# PowerAmplifier_Control.net
KiCad netlist of a schematic drawn in Altium Designer
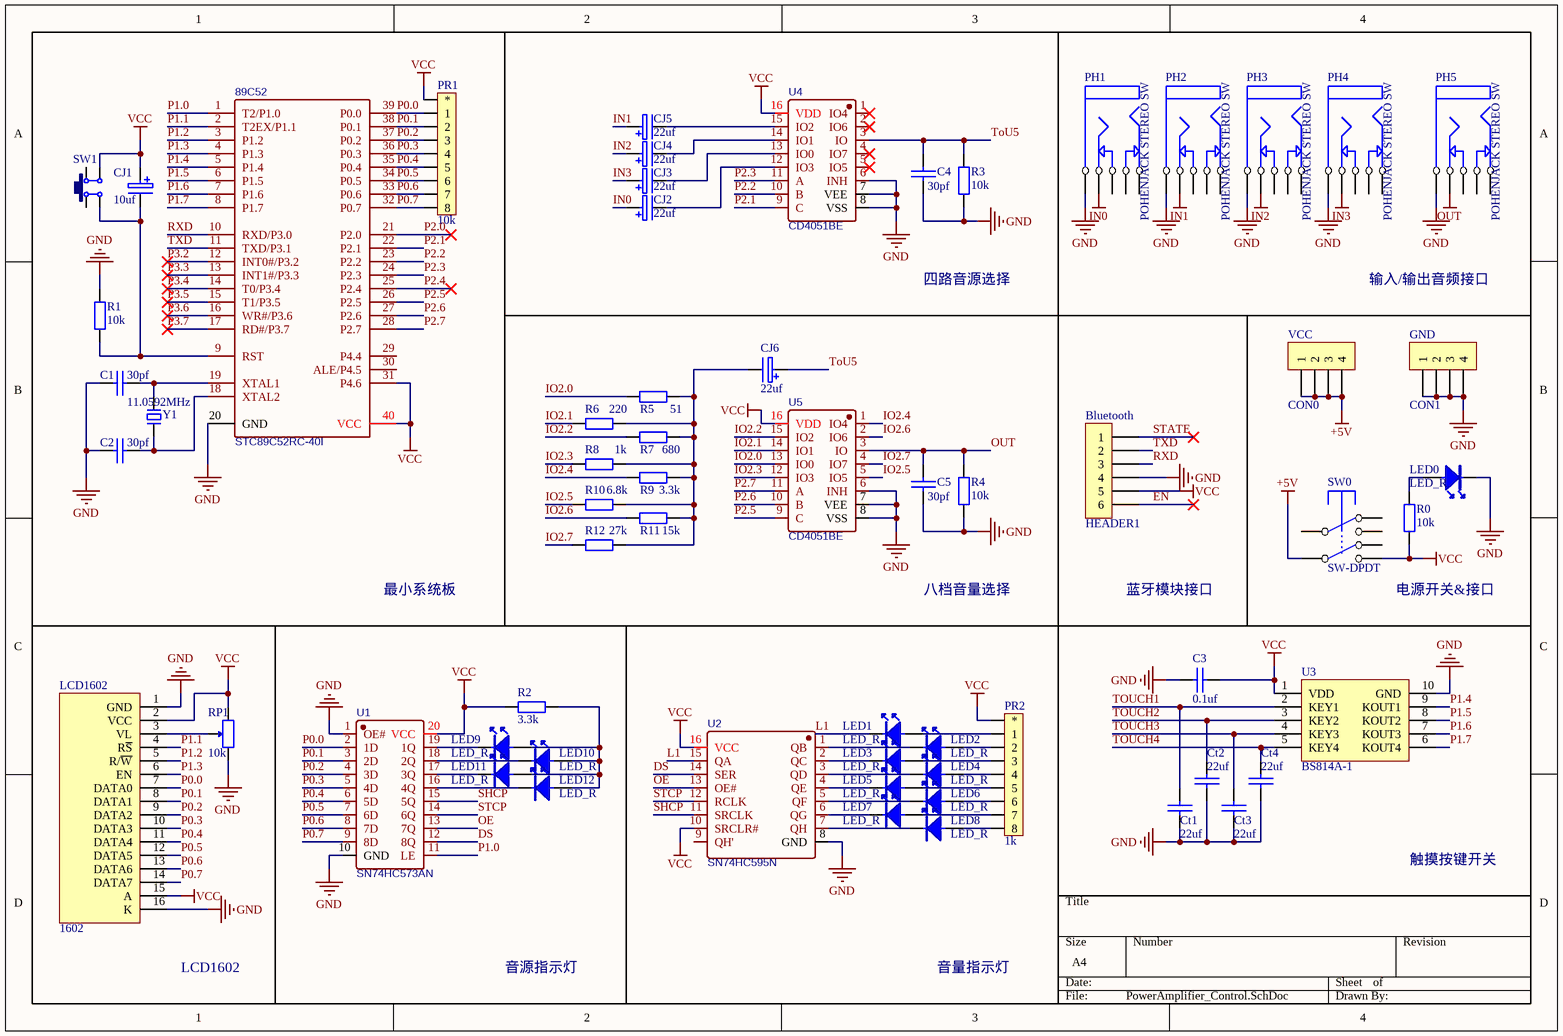
[diagram p0: PowerAmplifier_Control.SchDoc]

(export (version "E")
  (design (tool "Eeschema 10.0.6"))
  (components
    (comp (ref "89C52")
      (value "STC89C52RC-40I")
      (footprint "DIP-40_LS15.24-L52.58-W13.97-PITCH2.54")
      (fields (field (name "BOM_SUPPLIER PART") "C14022"))
      (libsource (lib "电子时钟元件库") (part "STC89C52RC-40I"))
    )
    (comp (ref "Bluetooth")
      (value "HEADER1")
      (footprint "sip-6")
      (description "Connector")
      (libsource (lib "基地库3.0mini") (part "CON6"))
    )
    (comp (ref "C1") (value "30pf") (footprint "1206") (libsource (lib "基地库3.0mini") (part "CAP1")))
    (comp (ref "C2") (value "30pf") (footprint "1206") (libsource (lib "基地库3.0mini") (part "CAP1")))
    (comp (ref "C3") (value "0.1uf") (footprint "1206") (libsource (lib "基地库3.0mini") (part "CAP1")))
    (comp (ref "C4") (value "30pf") (footprint "1206") (libsource (lib "基地库3.0mini") (part "CAP1")))
    (comp (ref "C5") (value "30pf") (footprint "1206") (libsource (lib "基地库3.0mini") (part "CAP1")))
    (comp (ref "CJ1") (value "10uf") (footprint "CAO1") (libsource (lib "基地库3.0mini") (part "CAP3")))
    (comp (ref "CJ2") (value "22uf") (footprint "CAO1") (libsource (lib "基地库3.0mini") (part "CAP3")))
    (comp (ref "CJ3") (value "22uf") (footprint "CAO1") (libsource (lib "基地库3.0mini") (part "CAP3")))
    (comp (ref "CJ4") (value "22uf") (footprint "CAO1") (libsource (lib "基地库3.0mini") (part "CAP3")))
    (comp (ref "CJ5") (value "22uf") (footprint "CAO1") (libsource (lib "基地库3.0mini") (part "CAP3")))
    (comp (ref "CJ6") (value "22uf") (footprint "CAO1") (libsource (lib "基地库3.0mini") (part "CAP3")))
    (comp (ref "Ct1") (value "22uf") (footprint "1206") (libsource (lib "基地库3.0mini") (part "CAP1")))
    (comp (ref "Ct2") (value "22uf") (footprint "1206") (libsource (lib "基地库3.0mini") (part "CAP1")))
    (comp (ref "Ct3") (value "22uf") (footprint "1206") (libsource (lib "基地库3.0mini") (part "CAP1")))
    (comp (ref "Ct4") (value "22uf") (footprint "1206") (libsource (lib "基地库3.0mini") (part "CAP1")))
    (comp (ref "GND")
      (value "CON1")
      (footprint "sip-4")
      (description "Connector")
      (libsource (lib "基地库3.0mini") (part "CON4"))
    )
    (comp (ref "LCD1602") (value "1602") (footprint "1602") (libsource (lib "基地库3.0mini") (part "1602")))
    (comp (ref "LED0") (value "LED_R") (footprint "LED_1206") (libsource (lib "基地库3.0mini") (part "LED")))
    (comp (ref "LED1") (value "LED_R") (footprint "LED_1206") (libsource (lib "基地库3.0mini") (part "LED")))
    (comp (ref "LED2") (value "LED_R") (footprint "LED_1206") (libsource (lib "基地库3.0mini") (part "LED")))
    (comp (ref "LED3") (value "LED_R") (footprint "LED_1206") (libsource (lib "基地库3.0mini") (part "LED")))
    (comp (ref "LED4") (value "LED_R") (footprint "LED_1206") (libsource (lib "基地库3.0mini") (part "LED")))
    (comp (ref "LED5") (value "LED_R") (footprint "LED_1206") (libsource (lib "基地库3.0mini") (part "LED")))
    (comp (ref "LED6") (value "LED_R") (footprint "LED_1206") (libsource (lib "基地库3.0mini") (part "LED")))
    (comp (ref "LED7") (value "LED_R") (footprint "LED_1206") (libsource (lib "基地库3.0mini") (part "LED")))
    (comp (ref "LED8") (value "LED_R") (footprint "LED_1206") (libsource (lib "基地库3.0mini") (part "LED")))
    (comp (ref "LED9") (value "LED_R") (footprint "LED_1206") (libsource (lib "基地库3.0mini") (part "LED")))
    (comp (ref "LED10") (value "LED_R") (footprint "LED_1206") (libsource (lib "基地库3.0mini") (part "LED")))
    (comp (ref "LED11") (value "LED_R") (footprint "LED_1206") (libsource (lib "基地库3.0mini") (part "LED")))
    (comp (ref "LED12") (value "LED_R") (footprint "LED_1206") (libsource (lib "基地库3.0mini") (part "LED")))
    (comp (ref "PH1")
      (value "POHENJACK STEREO SW")
      (footprint "POHENJACK STEREO SW")
      (libsource (lib "电子电路集成库") (part "POHENJACK STEREO SW"))
    )
    (comp (ref "PH2")
      (value "POHENJACK STEREO SW")
      (footprint "POHENJACK STEREO SW")
      (libsource (lib "电子电路集成库") (part "POHENJACK STEREO SW"))
    )
    (comp (ref "PH3")
      (value "POHENJACK STEREO SW")
      (footprint "POHENJACK STEREO SW")
      (libsource (lib "电子电路集成库") (part "POHENJACK STEREO SW"))
    )
    (comp (ref "PH4")
      (value "POHENJACK STEREO SW")
      (footprint "POHENJACK STEREO SW")
      (libsource (lib "电子电路集成库") (part "POHENJACK STEREO SW"))
    )
    (comp (ref "PH5")
      (value "POHENJACK STEREO SW")
      (footprint "POHENJACK STEREO SW")
      (libsource (lib "电子电路集成库") (part "POHENJACK STEREO SW"))
    )
    (comp (ref "PR1") (value "10k") (footprint "RP1") (libsource (lib "基地库3.0mini") (part "PRES1")))
    (comp (ref "PR2") (value "1k") (footprint "RP1") (libsource (lib "基地库3.0mini") (part "PRES1")))
    (comp (ref "R0")
      (value "10k")
      (footprint "AXIAL0.4")
      (description "贴片电阻")
      (fields (field (name "版权归属") "源创客"))
      (libsource (lib "9-电阻-电容-电感") (part "R"))
    )
    (comp (ref "R1")
      (value "10k")
      (footprint "AXIAL0.4")
      (description "贴片电阻")
      (fields (field (name "版权归属") "源创客"))
      (libsource (lib "9-电阻-电容-电感") (part "R"))
    )
    (comp (ref "R2")
      (value "3.3k")
      (footprint "AXIAL0.4")
      (description "贴片电阻")
      (fields (field (name "版权归属") "源创客"))
      (libsource (lib "9-电阻-电容-电感") (part "R"))
    )
    (comp (ref "R3")
      (value "10k")
      (footprint "AXIAL0.4")
      (description "贴片电阻")
      (fields (field (name "版权归属") "源创客"))
      (libsource (lib "9-电阻-电容-电感") (part "R"))
    )
    (comp (ref "R4")
      (value "10k")
      (footprint "AXIAL0.4")
      (description "贴片电阻")
      (fields (field (name "版权归属") "源创客"))
      (libsource (lib "9-电阻-电容-电感") (part "R"))
    )
    (comp (ref "R5")
      (value "51")
      (footprint "AXIAL0.4")
      (description "贴片电阻")
      (fields (field (name "版权归属") "源创客"))
      (libsource (lib "9-电阻-电容-电感") (part "R"))
    )
    (comp (ref "R6")
      (value "220")
      (footprint "AXIAL0.4")
      (description "贴片电阻")
      (fields (field (name "版权归属") "源创客"))
      (libsource (lib "9-电阻-电容-电感") (part "R"))
    )
    (comp (ref "R7")
      (value "680")
      (footprint "AXIAL0.4")
      (description "贴片电阻")
      (fields (field (name "版权归属") "源创客"))
      (libsource (lib "9-电阻-电容-电感") (part "R"))
    )
    (comp (ref "R8")
      (value "1k")
      (footprint "AXIAL0.4")
      (description "贴片电阻")
      (fields (field (name "版权归属") "源创客"))
      (libsource (lib "9-电阻-电容-电感") (part "R"))
    )
    (comp (ref "R9")
      (value "3.3k")
      (footprint "AXIAL0.4")
      (description "贴片电阻")
      (fields (field (name "版权归属") "源创客"))
      (libsource (lib "9-电阻-电容-电感") (part "R"))
    )
    (comp (ref "R10")
      (value "6.8k")
      (footprint "AXIAL0.4")
      (description "贴片电阻")
      (fields (field (name "版权归属") "源创客"))
      (libsource (lib "9-电阻-电容-电感") (part "R"))
    )
    (comp (ref "R11")
      (value "15k")
      (footprint "AXIAL0.4")
      (description "贴片电阻")
      (fields (field (name "版权归属") "源创客"))
      (libsource (lib "9-电阻-电容-电感") (part "R"))
    )
    (comp (ref "R12")
      (value "27k")
      (footprint "AXIAL0.4")
      (description "贴片电阻")
      (fields (field (name "版权归属") "源创客"))
      (libsource (lib "9-电阻-电容-电感") (part "R"))
    )
    (comp (ref "RP1")
      (value "10k")
      (footprint "3296W")
      (description "插件单联电位器")
      (fields (field (name "版权归属") "源创客"))
      (libsource (lib "9-电阻-电容-电感") (part "RP-ID"))
    )
    (comp (ref "SW0") (value "SW-DPDT") (footprint "SWH7*7") (libsource (lib "基地库3.0mini") (part "SW-DPDT")))
    (comp (ref "SW1")
      (value "6x6x5")
      (footprint "TSW DIP-6*6*6")
      (description "直插6x6轻触开关")
      (fields (field (name "版权归属") "源创客"))
      (libsource (lib "5-按键-开关") (part "TSW DIP-6x6"))
    )
    (comp (ref "U1")
      (value "SN74HC573AN")
      (footprint "DIP-20_L26.8-W6.4-P2.54-LS7.6-BL")
      (fields (field (name "BOM_SUPPLIER PART") "C5196"))
      (libsource (lib "74HC573AN") (part "SN74HC573AN"))
    )
    (comp (ref "U2")
      (value "SN74HC595N")
      (footprint "DIP-16_L19.8-W6.5-P2.54-LS7.6-BL")
      (fields (field (name "BOM_SUPPLIER PART") "C78711"))
      (libsource (lib "74HC595N") (part "SN74HC595N"))
    )
    (comp (ref "U3")
      (value "BS814A-1")
      (footprint "MSOP10_N")
      (description "4键电容触摸按键芯片")
      (fields (field (name "版权归属") "源创客"))
      (libsource (lib "14-IC芯片") (part "BS814A"))
    )
    (comp (ref "U4")
      (value "CD4051BE")
      (footprint "DIP-16_L20.0-W6.4-P2.54-LS7.6-BL")
      (fields (field (name "BOM_SUPPLIER PART") "C5200"))
      (libsource (lib "CD4051BE") (part "CD4051BE"))
    )
    (comp (ref "U5")
      (value "CD4051BE")
      (footprint "DIP-16_L20.0-W6.4-P2.54-LS7.6-BL")
      (fields (field (name "BOM_SUPPLIER PART") "C5200"))
      (libsource (lib "CD4051BE") (part "CD4051BE"))
    )
    (comp (ref "VCC")
      (value "CON0")
      (footprint "sip-4")
      (description "Connector")
      (libsource (lib "基地库3.0mini") (part "CON4"))
    )
    (comp (ref "Y1")
      (value "11.0592MHz")
      (footprint "OSC HC-49S")
      (description "2脚无源脚晶振")
      (fields (field (name "版权归属") "源创客"))
      (libsource (lib "6-保险丝-晶振") (part "XTAL-2P"))
    )
  )
  (nets
    (net (code "1") (name "+5V") (class "Default")
      (node (ref "SW0") (pin "5") (pinfunction "5_5") (pintype "passive"))
      (node (ref "VCC") (pin "1") (pinfunction "1_1") (pintype "passive"))
      (node (ref "VCC") (pin "2") (pinfunction "2_2") (pintype "passive"))
      (node (ref "VCC") (pin "3") (pinfunction "3_3") (pintype "passive"))
      (node (ref "VCC") (pin "4") (pinfunction "4_4") (pintype "passive"))
    )
    (net (code "2") (name "/DS") (class "Default")
      (node (ref "U1") (pin "12") (pinfunction "8Q_12") (pintype "passive"))
      (node (ref "U2") (pin "14") (pinfunction "SER_14") (pintype "passive"))
    )
    (net (code "3") (name "/EN") (class "Default")
      (node (ref "Bluetooth") (pin "6") (pinfunction "6_6") (pintype "passive+no_connect"))
    )
    (net (code "4") (name "/IO2.0") (class "Default")
      (node (ref "R5") (pin "1") (pinfunction "1_1") (pintype "passive"))
      (node (ref "U5") (pin "13") (pinfunction "IO0_13") (pintype "passive"))
    )
    (net (code "5") (name "/IO2.1") (class "Default")
      (node (ref "R6") (pin "1") (pinfunction "1_1") (pintype "passive"))
      (node (ref "U5") (pin "14") (pinfunction "IO1_14") (pintype "passive"))
    )
    (net (code "6") (name "/IO2.2") (class "Default")
      (node (ref "R7") (pin "1") (pinfunction "1_1") (pintype "passive"))
      (node (ref "U5") (pin "15") (pinfunction "IO2_15") (pintype "passive"))
    )
    (net (code "7") (name "/IO2.3") (class "Default")
      (node (ref "R8") (pin "1") (pinfunction "1_1") (pintype "passive"))
      (node (ref "U5") (pin "12") (pinfunction "IO3_12") (pintype "passive"))
    )
    (net (code "8") (name "/IO2.4") (class "Default")
      (node (ref "R9") (pin "1") (pinfunction "1_1") (pintype "passive"))
      (node (ref "U5") (pin "1") (pinfunction "IO4_1") (pintype "passive"))
    )
    (net (code "9") (name "/IO2.5") (class "Default")
      (node (ref "R10") (pin "1") (pinfunction "1_1") (pintype "passive"))
      (node (ref "U5") (pin "5") (pinfunction "IO5_5") (pintype "passive"))
    )
    (net (code "10") (name "/IO2.6") (class "Default")
      (node (ref "R11") (pin "1") (pinfunction "1_1") (pintype "passive"))
      (node (ref "U5") (pin "2") (pinfunction "IO6_2") (pintype "passive"))
    )
    (net (code "11") (name "/IO2.7") (class "Default")
      (node (ref "R12") (pin "1") (pinfunction "1_1") (pintype "passive"))
      (node (ref "U5") (pin "4") (pinfunction "IO7_4") (pintype "passive"))
    )
    (net (code "12") (name "/L1") (class "Default")
      (node (ref "LED1") (pin "2") (pinfunction "2_2") (pintype "passive"))
      (node (ref "U2") (pin "15") (pinfunction "QA_15") (pintype "passive"))
    )
    (net (code "13") (name "/OE") (class "Default")
      (node (ref "U1") (pin "13") (pinfunction "7Q_13") (pintype "passive"))
      (node (ref "U2") (pin "13") (pinfunction "OE#_13") (pintype "passive"))
    )
    (net (code "14") (name "/P0.0") (class "Default")
      (node (ref "89C52") (pin "39") (pinfunction "P0.0_39") (pintype "passive"))
      (node (ref "LCD1602") (pin "7") (pinfunction "DATA0_7") (pintype "passive"))
      (node (ref "PR1") (pin "2") (pinfunction "1_2") (pintype "passive"))
      (node (ref "U1") (pin "2") (pinfunction "1D_2") (pintype "passive"))
    )
    (net (code "15") (name "/P0.1") (class "Default")
      (node (ref "89C52") (pin "38") (pinfunction "P0.1_38") (pintype "passive"))
      (node (ref "LCD1602") (pin "8") (pinfunction "DATA1_8") (pintype "passive"))
      (node (ref "PR1") (pin "3") (pinfunction "2_3") (pintype "passive"))
      (node (ref "U1") (pin "3") (pinfunction "2D_3") (pintype "passive"))
    )
    (net (code "16") (name "/P0.2") (class "Default")
      (node (ref "89C52") (pin "37") (pinfunction "P0.2_37") (pintype "passive"))
      (node (ref "LCD1602") (pin "9") (pinfunction "DATA2_9") (pintype "passive"))
      (node (ref "PR1") (pin "4") (pinfunction "3_4") (pintype "passive"))
      (node (ref "U1") (pin "4") (pinfunction "3D_4") (pintype "passive"))
    )
    (net (code "17") (name "/P0.3") (class "Default")
      (node (ref "89C52") (pin "36") (pinfunction "P0.3_36") (pintype "passive"))
      (node (ref "LCD1602") (pin "10") (pinfunction "DATA3_10") (pintype "passive"))
      (node (ref "PR1") (pin "5") (pinfunction "4_5") (pintype "passive"))
      (node (ref "U1") (pin "5") (pinfunction "4D_5") (pintype "passive"))
    )
    (net (code "18") (name "/P0.4") (class "Default")
      (node (ref "89C52") (pin "35") (pinfunction "P0.4_35") (pintype "passive"))
      (node (ref "LCD1602") (pin "11") (pinfunction "DATA4_11") (pintype "passive"))
      (node (ref "PR1") (pin "6") (pinfunction "5_6") (pintype "passive"))
      (node (ref "U1") (pin "6") (pinfunction "5D_6") (pintype "passive"))
    )
    (net (code "19") (name "/P0.5") (class "Default")
      (node (ref "89C52") (pin "34") (pinfunction "P0.5_34") (pintype "passive"))
      (node (ref "LCD1602") (pin "12") (pinfunction "DATA5_12") (pintype "passive"))
      (node (ref "PR1") (pin "7") (pinfunction "6_7") (pintype "passive"))
      (node (ref "U1") (pin "7") (pinfunction "6D_7") (pintype "passive"))
    )
    (net (code "20") (name "/P0.6") (class "Default")
      (node (ref "89C52") (pin "33") (pinfunction "P0.6_33") (pintype "passive"))
      (node (ref "LCD1602") (pin "13") (pinfunction "DATA6_13") (pintype "passive"))
      (node (ref "PR1") (pin "8") (pinfunction "7_8") (pintype "passive"))
      (node (ref "U1") (pin "8") (pinfunction "7D_8") (pintype "passive"))
    )
    (net (code "21") (name "/P0.7") (class "Default")
      (node (ref "89C52") (pin "32") (pinfunction "P0.7_32") (pintype "passive"))
      (node (ref "LCD1602") (pin "14") (pinfunction "DATA7_14") (pintype "passive"))
      (node (ref "PR1") (pin "9") (pinfunction "8_9") (pintype "passive"))
      (node (ref "U1") (pin "9") (pinfunction "8D_9") (pintype "passive"))
    )
    (net (code "22") (name "/P1.0") (class "Default")
      (node (ref "89C52") (pin "1") (pinfunction "T2/P1.0_1") (pintype "passive"))
      (node (ref "U1") (pin "11") (pinfunction "LE_11") (pintype "passive"))
    )
    (net (code "23") (name "/P1.1") (class "Default")
      (node (ref "89C52") (pin "2") (pinfunction "T2EX/P1.1_2") (pintype "passive"))
      (node (ref "LCD1602") (pin "4") (pinfunction "R~{S}_4") (pintype "passive"))
    )
    (net (code "24") (name "/P1.2") (class "Default")
      (node (ref "89C52") (pin "3") (pinfunction "P1.2_3") (pintype "passive"))
      (node (ref "LCD1602") (pin "5") (pinfunction "R/~{W}_5") (pintype "passive"))
    )
    (net (code "25") (name "/P1.3") (class "Default")
      (node (ref "89C52") (pin "4") (pinfunction "P1.3_4") (pintype "passive"))
      (node (ref "LCD1602") (pin "6") (pinfunction "EN_6") (pintype "passive"))
    )
    (net (code "26") (name "/P1.4") (class "Default")
      (node (ref "89C52") (pin "5") (pinfunction "P1.4_5") (pintype "passive"))
      (node (ref "U3") (pin "9") (pinfunction "KOUT1_9") (pintype "passive"))
    )
    (net (code "27") (name "/P1.5") (class "Default")
      (node (ref "89C52") (pin "6") (pinfunction "P1.5_6") (pintype "passive"))
      (node (ref "U3") (pin "8") (pinfunction "KOUT2_8") (pintype "passive"))
    )
    (net (code "28") (name "/P1.6") (class "Default")
      (node (ref "89C52") (pin "7") (pinfunction "P1.6_7") (pintype "passive"))
      (node (ref "U3") (pin "7") (pinfunction "KOUT3_7") (pintype "passive"))
    )
    (net (code "29") (name "/P1.7") (class "Default")
      (node (ref "89C52") (pin "8") (pinfunction "P1.7_8") (pintype "passive"))
      (node (ref "U3") (pin "6") (pinfunction "KOUT4_6") (pintype "passive"))
    )
    (net (code "30") (name "/P2.0") (class "Default")
      (node (ref "89C52") (pin "21") (pinfunction "P2.0_21") (pintype "passive+no_connect"))
    )
    (net (code "31") (name "/P2.1") (class "Default")
      (node (ref "89C52") (pin "22") (pinfunction "P2.1_22") (pintype "passive"))
      (node (ref "U4") (pin "9") (pinfunction "C_9") (pintype "passive"))
    )
    (net (code "32") (name "/P2.2") (class "Default")
      (node (ref "89C52") (pin "23") (pinfunction "P2.2_23") (pintype "passive"))
      (node (ref "U4") (pin "10") (pinfunction "B_10") (pintype "passive"))
    )
    (net (code "33") (name "/P2.3") (class "Default")
      (node (ref "89C52") (pin "24") (pinfunction "P2.3_24") (pintype "passive"))
      (node (ref "U4") (pin "11") (pinfunction "A_11") (pintype "passive"))
    )
    (net (code "34") (name "/P2.4") (class "Default")
      (node (ref "89C52") (pin "25") (pinfunction "P2.4_25") (pintype "passive+no_connect"))
    )
    (net (code "35") (name "/P2.5") (class "Default")
      (node (ref "89C52") (pin "26") (pinfunction "P2.5_26") (pintype "passive"))
      (node (ref "U5") (pin "9") (pinfunction "C_9") (pintype "passive"))
    )
    (net (code "36") (name "/P2.6") (class "Default")
      (node (ref "89C52") (pin "27") (pinfunction "P2.6_27") (pintype "passive"))
      (node (ref "U5") (pin "10") (pinfunction "B_10") (pintype "passive"))
    )
    (net (code "37") (name "/P2.7") (class "Default")
      (node (ref "89C52") (pin "28") (pinfunction "P2.7_28") (pintype "passive"))
      (node (ref "U5") (pin "11") (pinfunction "A_11") (pintype "passive"))
    )
    (net (code "38") (name "/P3.2") (class "Default")
      (node (ref "89C52") (pin "12") (pinfunction "INT0#/P3.2_12") (pintype "passive+no_connect"))
    )
    (net (code "39") (name "/P3.3") (class "Default")
      (node (ref "89C52") (pin "13") (pinfunction "INT1#/P3.3_13") (pintype "passive+no_connect"))
    )
    (net (code "40") (name "/P3.4") (class "Default")
      (node (ref "89C52") (pin "14") (pinfunction "T0/P3.4_14") (pintype "passive+no_connect"))
    )
    (net (code "41") (name "/P3.5") (class "Default")
      (node (ref "89C52") (pin "15") (pinfunction "T1/P3.5_15") (pintype "passive+no_connect"))
    )
    (net (code "42") (name "/P3.6") (class "Default")
      (node (ref "89C52") (pin "16") (pinfunction "WR#/P3.6_16") (pintype "passive+no_connect"))
    )
    (net (code "43") (name "/P3.7") (class "Default")
      (node (ref "89C52") (pin "17") (pinfunction "RD#/P3.7_17") (pintype "passive+no_connect"))
    )
    (net (code "44") (name "/RXD") (class "Default")
      (node (ref "89C52") (pin "10") (pinfunction "RXD/P3.0_10") (pintype "passive"))
      (node (ref "Bluetooth") (pin "3") (pinfunction "3_3") (pintype "passive"))
    )
    (net (code "45") (name "/SHCP") (class "Default")
      (node (ref "U1") (pin "15") (pinfunction "5Q_15") (pintype "passive"))
      (node (ref "U2") (pin "11") (pinfunction "SRCLK_11") (pintype "passive"))
    )
    (net (code "46") (name "/STATE") (class "Default")
      (node (ref "Bluetooth") (pin "1") (pinfunction "1_1") (pintype "passive+no_connect"))
    )
    (net (code "47") (name "/STCP") (class "Default")
      (node (ref "U1") (pin "14") (pinfunction "6Q_14") (pintype "passive"))
      (node (ref "U2") (pin "12") (pinfunction "RCLK_12") (pintype "passive"))
    )
    (net (code "48") (name "/TOUCH1") (class "Default")
      (node (ref "Ct1") (pin "1") (pinfunction "1_1") (pintype "passive"))
      (node (ref "U3") (pin "2") (pinfunction "KEY1_2") (pintype "passive"))
    )
    (net (code "49") (name "/TOUCH2") (class "Default")
      (node (ref "Ct2") (pin "1") (pinfunction "1_1") (pintype "passive"))
      (node (ref "U3") (pin "3") (pinfunction "KEY2_3") (pintype "passive"))
    )
    (net (code "50") (name "/TOUCH3") (class "Default")
      (node (ref "Ct3") (pin "1") (pinfunction "1_1") (pintype "passive"))
      (node (ref "U3") (pin "4") (pinfunction "KEY3_4") (pintype "passive"))
    )
    (net (code "51") (name "/TOUCH4") (class "Default")
      (node (ref "Ct4") (pin "1") (pinfunction "1_1") (pintype "passive"))
      (node (ref "U3") (pin "5") (pinfunction "KEY4_5") (pintype "passive"))
    )
    (net (code "52") (name "/TXD") (class "Default")
      (node (ref "89C52") (pin "11") (pinfunction "TXD/P3.1_11") (pintype "passive"))
      (node (ref "Bluetooth") (pin "2") (pinfunction "2_2") (pintype "passive"))
    )
    (net (code "53") (name "/ToU5") (class "Default")
      (node (ref "C4") (pin "1") (pinfunction "1_1") (pintype "passive"))
      (node (ref "CJ6") (pin "1") (pintype "passive"))
      (node (ref "R3") (pin "2") (pinfunction "2_2") (pintype "passive"))
      (node (ref "U4") (pin "3") (pinfunction "IO_3") (pintype "passive"))
    )
    (net (code "54") (name "GND") (class "Default")
      (node (ref "89C52") (pin "20") (pinfunction "GND_20") (pintype "passive"))
      (node (ref "Bluetooth") (pin "4") (pinfunction "4_4") (pintype "passive"))
      (node (ref "C1") (pin "2") (pinfunction "2_2") (pintype "passive"))
      (node (ref "C2") (pin "2") (pinfunction "2_2") (pintype "passive"))
      (node (ref "C3") (pin "1") (pinfunction "1_1") (pintype "passive"))
      (node (ref "C4") (pin "2") (pinfunction "2_2") (pintype "passive"))
      (node (ref "C5") (pin "2") (pinfunction "2_2") (pintype "passive"))
      (node (ref "Ct1") (pin "2") (pinfunction "2_2") (pintype "passive"))
      (node (ref "Ct2") (pin "2") (pinfunction "2_2") (pintype "passive"))
      (node (ref "Ct3") (pin "2") (pinfunction "2_2") (pintype "passive"))
      (node (ref "Ct4") (pin "2") (pinfunction "2_2") (pintype "passive"))
      (node (ref "GND") (pin "1") (pinfunction "1_1") (pintype "passive"))
      (node (ref "GND") (pin "2") (pinfunction "2_2") (pintype "passive"))
      (node (ref "GND") (pin "3") (pinfunction "3_3") (pintype "passive"))
      (node (ref "GND") (pin "4") (pinfunction "4_4") (pintype "passive"))
      (node (ref "LCD1602") (pin "1") (pinfunction "GND_1") (pintype "passive"))
      (node (ref "LCD1602") (pin "16") (pinfunction "K_16") (pintype "passive"))
      (node (ref "LED0") (pin "2") (pinfunction "2_2") (pintype "passive"))
      (node (ref "PH1") (pin "5") (pinfunction "E_5") (pintype "passive"))
      (node (ref "PH2") (pin "5") (pinfunction "E_5") (pintype "passive"))
      (node (ref "PH3") (pin "5") (pinfunction "E_5") (pintype "passive"))
      (node (ref "PH4") (pin "5") (pinfunction "E_5") (pintype "passive"))
      (node (ref "PH5") (pin "5") (pinfunction "E_5") (pintype "passive"))
      (node (ref "R1") (pin "1") (pinfunction "1_1") (pintype "passive"))
      (node (ref "R3") (pin "1") (pinfunction "1_1") (pintype "passive"))
      (node (ref "R4") (pin "1") (pinfunction "1_1") (pintype "passive"))
      (node (ref "RP1") (pin "1") (pinfunction "1_1") (pintype "passive"))
      (node (ref "U1") (pin "1") (pinfunction "OE#_1") (pintype "passive"))
      (node (ref "U1") (pin "10") (pinfunction "GND_10") (pintype "passive"))
      (node (ref "U2") (pin "8") (pinfunction "GND_8") (pintype "passive"))
      (node (ref "U3") (pin "10") (pinfunction "GND_10") (pintype "passive"))
      (node (ref "U4") (pin "6") (pinfunction "INH_6") (pintype "passive"))
      (node (ref "U4") (pin "7") (pinfunction "VEE_7") (pintype "passive"))
      (node (ref "U4") (pin "8") (pinfunction "VSS_8") (pintype "passive"))
      (node (ref "U5") (pin "6") (pinfunction "INH_6") (pintype "passive"))
      (node (ref "U5") (pin "7") (pinfunction "VEE_7") (pintype "passive"))
      (node (ref "U5") (pin "8") (pinfunction "VSS_8") (pintype "passive"))
    )
    (net (code "55") (name "IN0") (class "Default")
      (node (ref "CJ2") (pin "1") (pintype "passive"))
      (node (ref "PH1") (pin "4") (pinfunction "D_4") (pintype "passive"))
    )
    (net (code "56") (name "IN1") (class "Default")
      (node (ref "CJ5") (pin "1") (pintype "passive"))
      (node (ref "PH2") (pin "4") (pinfunction "D_4") (pintype "passive"))
    )
    (net (code "57") (name "IN2") (class "Default")
      (node (ref "CJ4") (pin "1") (pintype "passive"))
      (node (ref "PH3") (pin "4") (pinfunction "D_4") (pintype "passive"))
    )
    (net (code "58") (name "IN3") (class "Default")
      (node (ref "CJ3") (pin "1") (pintype "passive"))
      (node (ref "PH4") (pin "4") (pinfunction "D_4") (pintype "passive"))
    )
    (net (code "59") (name "Net-(89C52-RST)") (class "Default")
      (node (ref "89C52") (pin "9") (pinfunction "RST_9") (pintype "passive"))
      (node (ref "CJ1") (pin "2") (pintype "passive"))
      (node (ref "R1") (pin "2") (pinfunction "2_2") (pintype "passive"))
      (node (ref "SW1") (pin "4") (pinfunction "4_4") (pintype "passive"))
    )
    (net (code "60") (name "Net-(89C52-XTAL1)") (class "Default")
      (node (ref "89C52") (pin "19") (pinfunction "XTAL1_19") (pintype "passive"))
      (node (ref "C1") (pin "1") (pinfunction "1_1") (pintype "passive"))
      (node (ref "Y1") (pin "2") (pinfunction "2_2") (pintype "passive"))
    )
    (net (code "61") (name "Net-(89C52-XTAL2)") (class "Default")
      (node (ref "89C52") (pin "18") (pinfunction "XTAL2_18") (pintype "passive"))
      (node (ref "C2") (pin "1") (pinfunction "1_1") (pintype "passive"))
      (node (ref "Y1") (pin "1") (pinfunction "1_1") (pintype "passive"))
    )
    (net (code "62") (name "Net-(CJ6-Pad2)") (class "Default")
      (node (ref "CJ6") (pin "2") (pintype "passive"))
      (node (ref "R10") (pin "2") (pinfunction "2_2") (pintype "passive"))
      (node (ref "R11") (pin "2") (pinfunction "2_2") (pintype "passive"))
      (node (ref "R12") (pin "2") (pinfunction "2_2") (pintype "passive"))
      (node (ref "R5") (pin "2") (pinfunction "2_2") (pintype "passive"))
      (node (ref "R6") (pin "2") (pinfunction "2_2") (pintype "passive"))
      (node (ref "R7") (pin "2") (pinfunction "2_2") (pintype "passive"))
      (node (ref "R8") (pin "2") (pinfunction "2_2") (pintype "passive"))
      (node (ref "R9") (pin "2") (pinfunction "2_2") (pintype "passive"))
    )
    (net (code "63") (name "Net-(LCD1602-VL)") (class "Default")
      (node (ref "LCD1602") (pin "3") (pinfunction "VL_3") (pintype "passive"))
      (node (ref "RP1") (pin "2") (pinfunction "2_2") (pintype "passive"))
    )
    (net (code "64") (name "Net-(LED0-Pad1)") (class "Default")
      (node (ref "LED0") (pin "1") (pinfunction "1_1") (pintype "passive"))
      (node (ref "R0") (pin "1") (pinfunction "1_1") (pintype "passive"))
    )
    (net (code "65") (name "Net-(LED10-Pad1)") (class "Default")
      (node (ref "LED10") (pin "1") (pinfunction "1_1") (pintype "passive"))
      (node (ref "LED11") (pin "1") (pinfunction "1_1") (pintype "passive"))
      (node (ref "LED12") (pin "1") (pinfunction "1_1") (pintype "passive"))
      (node (ref "LED9") (pin "1") (pinfunction "1_1") (pintype "passive"))
      (node (ref "R2") (pin "1") (pinfunction "1_1") (pintype "passive"))
    )
    (net (code "66") (name "Net-(PR2-1)") (class "Default")
      (node (ref "LED1") (pin "1") (pinfunction "1_1") (pintype "passive"))
      (node (ref "PR2") (pin "2") (pinfunction "1_2") (pintype "passive"))
    )
    (net (code "67") (name "Net-(PR2-2)") (class "Default")
      (node (ref "LED2") (pin "1") (pinfunction "1_1") (pintype "passive"))
      (node (ref "PR2") (pin "3") (pinfunction "2_3") (pintype "passive"))
    )
    (net (code "68") (name "Net-(PR2-3)") (class "Default")
      (node (ref "LED3") (pin "1") (pinfunction "1_1") (pintype "passive"))
      (node (ref "PR2") (pin "4") (pinfunction "3_4") (pintype "passive"))
    )
    (net (code "69") (name "Net-(PR2-4)") (class "Default")
      (node (ref "LED4") (pin "1") (pinfunction "1_1") (pintype "passive"))
      (node (ref "PR2") (pin "5") (pinfunction "4_5") (pintype "passive"))
    )
    (net (code "70") (name "Net-(PR2-5)") (class "Default")
      (node (ref "LED5") (pin "1") (pinfunction "1_1") (pintype "passive"))
      (node (ref "PR2") (pin "6") (pinfunction "5_6") (pintype "passive"))
    )
    (net (code "71") (name "Net-(PR2-6)") (class "Default")
      (node (ref "LED6") (pin "1") (pinfunction "1_1") (pintype "passive"))
      (node (ref "PR2") (pin "7") (pinfunction "6_7") (pintype "passive"))
    )
    (net (code "72") (name "Net-(PR2-7)") (class "Default")
      (node (ref "LED7") (pin "1") (pinfunction "1_1") (pintype "passive"))
      (node (ref "PR2") (pin "8") (pinfunction "7_8") (pintype "passive"))
    )
    (net (code "73") (name "Net-(PR2-8)") (class "Default")
      (node (ref "LED8") (pin "1") (pinfunction "1_1") (pintype "passive"))
      (node (ref "PR2") (pin "9") (pinfunction "8_9") (pintype "passive"))
    )
    (net (code "74") (name "Net-(U1-1Q)") (class "Default")
      (node (ref "LED9") (pin "2") (pinfunction "2_2") (pintype "passive"))
      (node (ref "U1") (pin "19") (pinfunction "1Q_19") (pintype "passive"))
    )
    (net (code "75") (name "Net-(U1-2Q)") (class "Default")
      (node (ref "LED10") (pin "2") (pinfunction "2_2") (pintype "passive"))
      (node (ref "U1") (pin "18") (pinfunction "2Q_18") (pintype "passive"))
    )
    (net (code "76") (name "Net-(U1-3Q)") (class "Default")
      (node (ref "LED11") (pin "2") (pinfunction "2_2") (pintype "passive"))
      (node (ref "U1") (pin "17") (pinfunction "3Q_17") (pintype "passive"))
    )
    (net (code "77") (name "Net-(U1-4Q)") (class "Default")
      (node (ref "LED12") (pin "2") (pinfunction "2_2") (pintype "passive"))
      (node (ref "U1") (pin "16") (pinfunction "4Q_16") (pintype "passive"))
    )
    (net (code "78") (name "Net-(U2-QB)") (class "Default")
      (node (ref "LED2") (pin "2") (pinfunction "2_2") (pintype "passive"))
      (node (ref "U2") (pin "1") (pinfunction "QB_1") (pintype "passive"))
    )
    (net (code "79") (name "Net-(U2-QC)") (class "Default")
      (node (ref "LED3") (pin "2") (pinfunction "2_2") (pintype "passive"))
      (node (ref "U2") (pin "2") (pinfunction "QC_2") (pintype "passive"))
    )
    (net (code "80") (name "Net-(U2-QD)") (class "Default")
      (node (ref "LED4") (pin "2") (pinfunction "2_2") (pintype "passive"))
      (node (ref "U2") (pin "3") (pinfunction "QD_3") (pintype "passive"))
    )
    (net (code "81") (name "Net-(U2-QE)") (class "Default")
      (node (ref "LED5") (pin "2") (pinfunction "2_2") (pintype "passive"))
      (node (ref "U2") (pin "4") (pinfunction "QE_4") (pintype "passive"))
    )
    (net (code "82") (name "Net-(U2-QF)") (class "Default")
      (node (ref "LED6") (pin "2") (pinfunction "2_2") (pintype "passive"))
      (node (ref "U2") (pin "5") (pinfunction "QF_5") (pintype "passive"))
    )
    (net (code "83") (name "Net-(U2-QG)") (class "Default")
      (node (ref "LED7") (pin "2") (pinfunction "2_2") (pintype "passive"))
      (node (ref "U2") (pin "6") (pinfunction "QG_6") (pintype "passive"))
    )
    (net (code "84") (name "Net-(U2-QH)") (class "Default")
      (node (ref "LED8") (pin "2") (pinfunction "2_2") (pintype "passive"))
      (node (ref "U2") (pin "7") (pinfunction "QH_7") (pintype "passive"))
    )
    (net (code "85") (name "Net-(U4-IO0)") (class "Default")
      (node (ref "CJ3") (pin "2") (pintype "passive"))
      (node (ref "U4") (pin "13") (pinfunction "IO0_13") (pintype "passive"))
    )
    (net (code "86") (name "Net-(U4-IO1)") (class "Default")
      (node (ref "CJ4") (pin "2") (pintype "passive"))
      (node (ref "U4") (pin "14") (pinfunction "IO1_14") (pintype "passive"))
    )
    (net (code "87") (name "Net-(U4-IO2)") (class "Default")
      (node (ref "CJ5") (pin "2") (pintype "passive"))
      (node (ref "U4") (pin "15") (pinfunction "IO2_15") (pintype "passive"))
    )
    (net (code "88") (name "Net-(U4-IO3)") (class "Default")
      (node (ref "CJ2") (pin "2") (pintype "passive"))
      (node (ref "U4") (pin "12") (pinfunction "IO3_12") (pintype "passive"))
    )
    (net (code "89") (name "OUT") (class "Default")
      (node (ref "C5") (pin "1") (pinfunction "1_1") (pintype "passive"))
      (node (ref "PH5") (pin "4") (pinfunction "D_4") (pintype "passive"))
      (node (ref "R4") (pin "2") (pinfunction "2_2") (pintype "passive"))
      (node (ref "U5") (pin "3") (pinfunction "IO_3") (pintype "passive"))
    )
    (net (code "90") (name "VCC") (class "Default")
      (node (ref "89C52") (pin "31") (pinfunction "P4.6_31") (pintype "passive"))
      (node (ref "89C52") (pin "40") (pinfunction "VCC_40") (pintype "passive"))
      (node (ref "Bluetooth") (pin "5") (pinfunction "5_5") (pintype "passive"))
      (node (ref "C3") (pin "2") (pinfunction "2_2") (pintype "passive"))
      (node (ref "CJ1") (pin "1") (pintype "passive"))
      (node (ref "LCD1602") (pin "15") (pinfunction "A_15") (pintype "passive"))
      (node (ref "LCD1602") (pin "2") (pinfunction "VCC_2") (pintype "passive"))
      (node (ref "PR1") (pin "1") (pinfunction "*_1") (pintype "passive"))
      (node (ref "PR2") (pin "1") (pinfunction "*_1") (pintype "passive"))
      (node (ref "R0") (pin "2") (pinfunction "2_2") (pintype "passive"))
      (node (ref "R2") (pin "2") (pinfunction "2_2") (pintype "passive"))
      (node (ref "RP1") (pin "3") (pinfunction "3_3") (pintype "passive"))
      (node (ref "SW0") (pin "4") (pinfunction "4_4") (pintype "passive"))
      (node (ref "SW1") (pin "3") (pinfunction "3_3") (pintype "passive"))
      (node (ref "U1") (pin "20") (pinfunction "VCC_20") (pintype "passive"))
      (node (ref "U2") (pin "10") (pinfunction "SRCLR#_10") (pintype "passive"))
      (node (ref "U2") (pin "16") (pinfunction "VCC_16") (pintype "passive"))
      (node (ref "U3") (pin "1") (pinfunction "VDD_1") (pintype "passive"))
      (node (ref "U4") (pin "16") (pinfunction "VDD_16") (pintype "passive"))
      (node (ref "U5") (pin "16") (pinfunction "VDD_16") (pintype "passive"))
    )
    (net (code "91") (name "unconnected-(89C52-ALE{slash}P4.5-Pad30)") (class "Default")
      (node (ref "89C52") (pin "30") (pinfunction "ALE/P4.5_30") (pintype "passive"))
    )
    (net (code "92") (name "unconnected-(89C52-P4.4-Pad29)") (class "Default")
      (node (ref "89C52") (pin "29") (pinfunction "P4.4_29") (pintype "passive"))
    )
    (net (code "93") (name "unconnected-(PH1-A-Pad1)") (class "Default")
      (node (ref "PH1") (pin "1") (pinfunction "A_1") (pintype "passive"))
    )
    (net (code "94") (name "unconnected-(PH1-B-Pad2)") (class "Default")
      (node (ref "PH1") (pin "2") (pinfunction "B_2") (pintype "passive"))
    )
    (net (code "95") (name "unconnected-(PH1-C-Pad3)") (class "Default")
      (node (ref "PH1") (pin "3") (pinfunction "C_3") (pintype "passive"))
    )
    (net (code "96") (name "unconnected-(PH2-A-Pad1)") (class "Default")
      (node (ref "PH2") (pin "1") (pinfunction "A_1") (pintype "passive"))
    )
    (net (code "97") (name "unconnected-(PH2-B-Pad2)") (class "Default")
      (node (ref "PH2") (pin "2") (pinfunction "B_2") (pintype "passive"))
    )
    (net (code "98") (name "unconnected-(PH2-C-Pad3)") (class "Default")
      (node (ref "PH2") (pin "3") (pinfunction "C_3") (pintype "passive"))
    )
    (net (code "99") (name "unconnected-(PH3-A-Pad1)") (class "Default")
      (node (ref "PH3") (pin "1") (pinfunction "A_1") (pintype "passive"))
    )
    (net (code "100") (name "unconnected-(PH3-B-Pad2)") (class "Default")
      (node (ref "PH3") (pin "2") (pinfunction "B_2") (pintype "passive"))
    )
    (net (code "101") (name "unconnected-(PH3-C-Pad3)") (class "Default")
      (node (ref "PH3") (pin "3") (pinfunction "C_3") (pintype "passive"))
    )
    (net (code "102") (name "unconnected-(PH4-A-Pad1)") (class "Default")
      (node (ref "PH4") (pin "1") (pinfunction "A_1") (pintype "passive"))
    )
    (net (code "103") (name "unconnected-(PH4-B-Pad2)") (class "Default")
      (node (ref "PH4") (pin "2") (pinfunction "B_2") (pintype "passive"))
    )
    (net (code "104") (name "unconnected-(PH4-C-Pad3)") (class "Default")
      (node (ref "PH4") (pin "3") (pinfunction "C_3") (pintype "passive"))
    )
    (net (code "105") (name "unconnected-(PH5-A-Pad1)") (class "Default")
      (node (ref "PH5") (pin "1") (pinfunction "A_1") (pintype "passive"))
    )
    (net (code "106") (name "unconnected-(PH5-B-Pad2)") (class "Default")
      (node (ref "PH5") (pin "2") (pinfunction "B_2") (pintype "passive"))
    )
    (net (code "107") (name "unconnected-(PH5-C-Pad3)") (class "Default")
      (node (ref "PH5") (pin "3") (pinfunction "C_3") (pintype "passive"))
    )
    (net (code "108") (name "unconnected-(SW0-Pad1)") (class "Default")
      (node (ref "SW0") (pin "1") (pinfunction "1_1") (pintype "passive"))
    )
    (net (code "109") (name "unconnected-(SW0-Pad2)") (class "Default")
      (node (ref "SW0") (pin "2") (pinfunction "2_2") (pintype "passive"))
    )
    (net (code "110") (name "unconnected-(SW0-Pad3)") (class "Default")
      (node (ref "SW0") (pin "3") (pinfunction "3_3") (pintype "passive"))
    )
    (net (code "111") (name "unconnected-(SW0-Pad6)") (class "Default")
      (node (ref "SW0") (pin "6") (pinfunction "6_6") (pintype "passive"))
    )
    (net (code "112") (name "unconnected-(SW1-Pad1)") (class "Default")
      (node (ref "SW1") (pin "1") (pinfunction "1_1") (pintype "passive"))
    )
    (net (code "113") (name "unconnected-(SW1-Pad2)") (class "Default")
      (node (ref "SW1") (pin "2") (pinfunction "2_2") (pintype "passive"))
    )
    (net (code "114") (name "unconnected-(U2-QH'-Pad9)") (class "Default")
      (node (ref "U2") (pin "9") (pinfunction "QH'_9") (pintype "passive"))
    )
    (net (code "115") (name "unconnected-(U4-IO4-Pad1)") (class "Default")
      (node (ref "U4") (pin "1") (pinfunction "IO4_1") (pintype "passive+no_connect"))
    )
    (net (code "116") (name "unconnected-(U4-IO5-Pad5)") (class "Default")
      (node (ref "U4") (pin "5") (pinfunction "IO5_5") (pintype "passive+no_connect"))
    )
    (net (code "117") (name "unconnected-(U4-IO6-Pad2)") (class "Default")
      (node (ref "U4") (pin "2") (pinfunction "IO6_2") (pintype "passive+no_connect"))
    )
    (net (code "118") (name "unconnected-(U4-IO7-Pad4)") (class "Default")
      (node (ref "U4") (pin "4") (pinfunction "IO7_4") (pintype "passive+no_connect"))
    )
  )
)
